# bldc_driver_board_easyeda.net
KiCad netlist of a schematic drawn in EasyEDA Pro
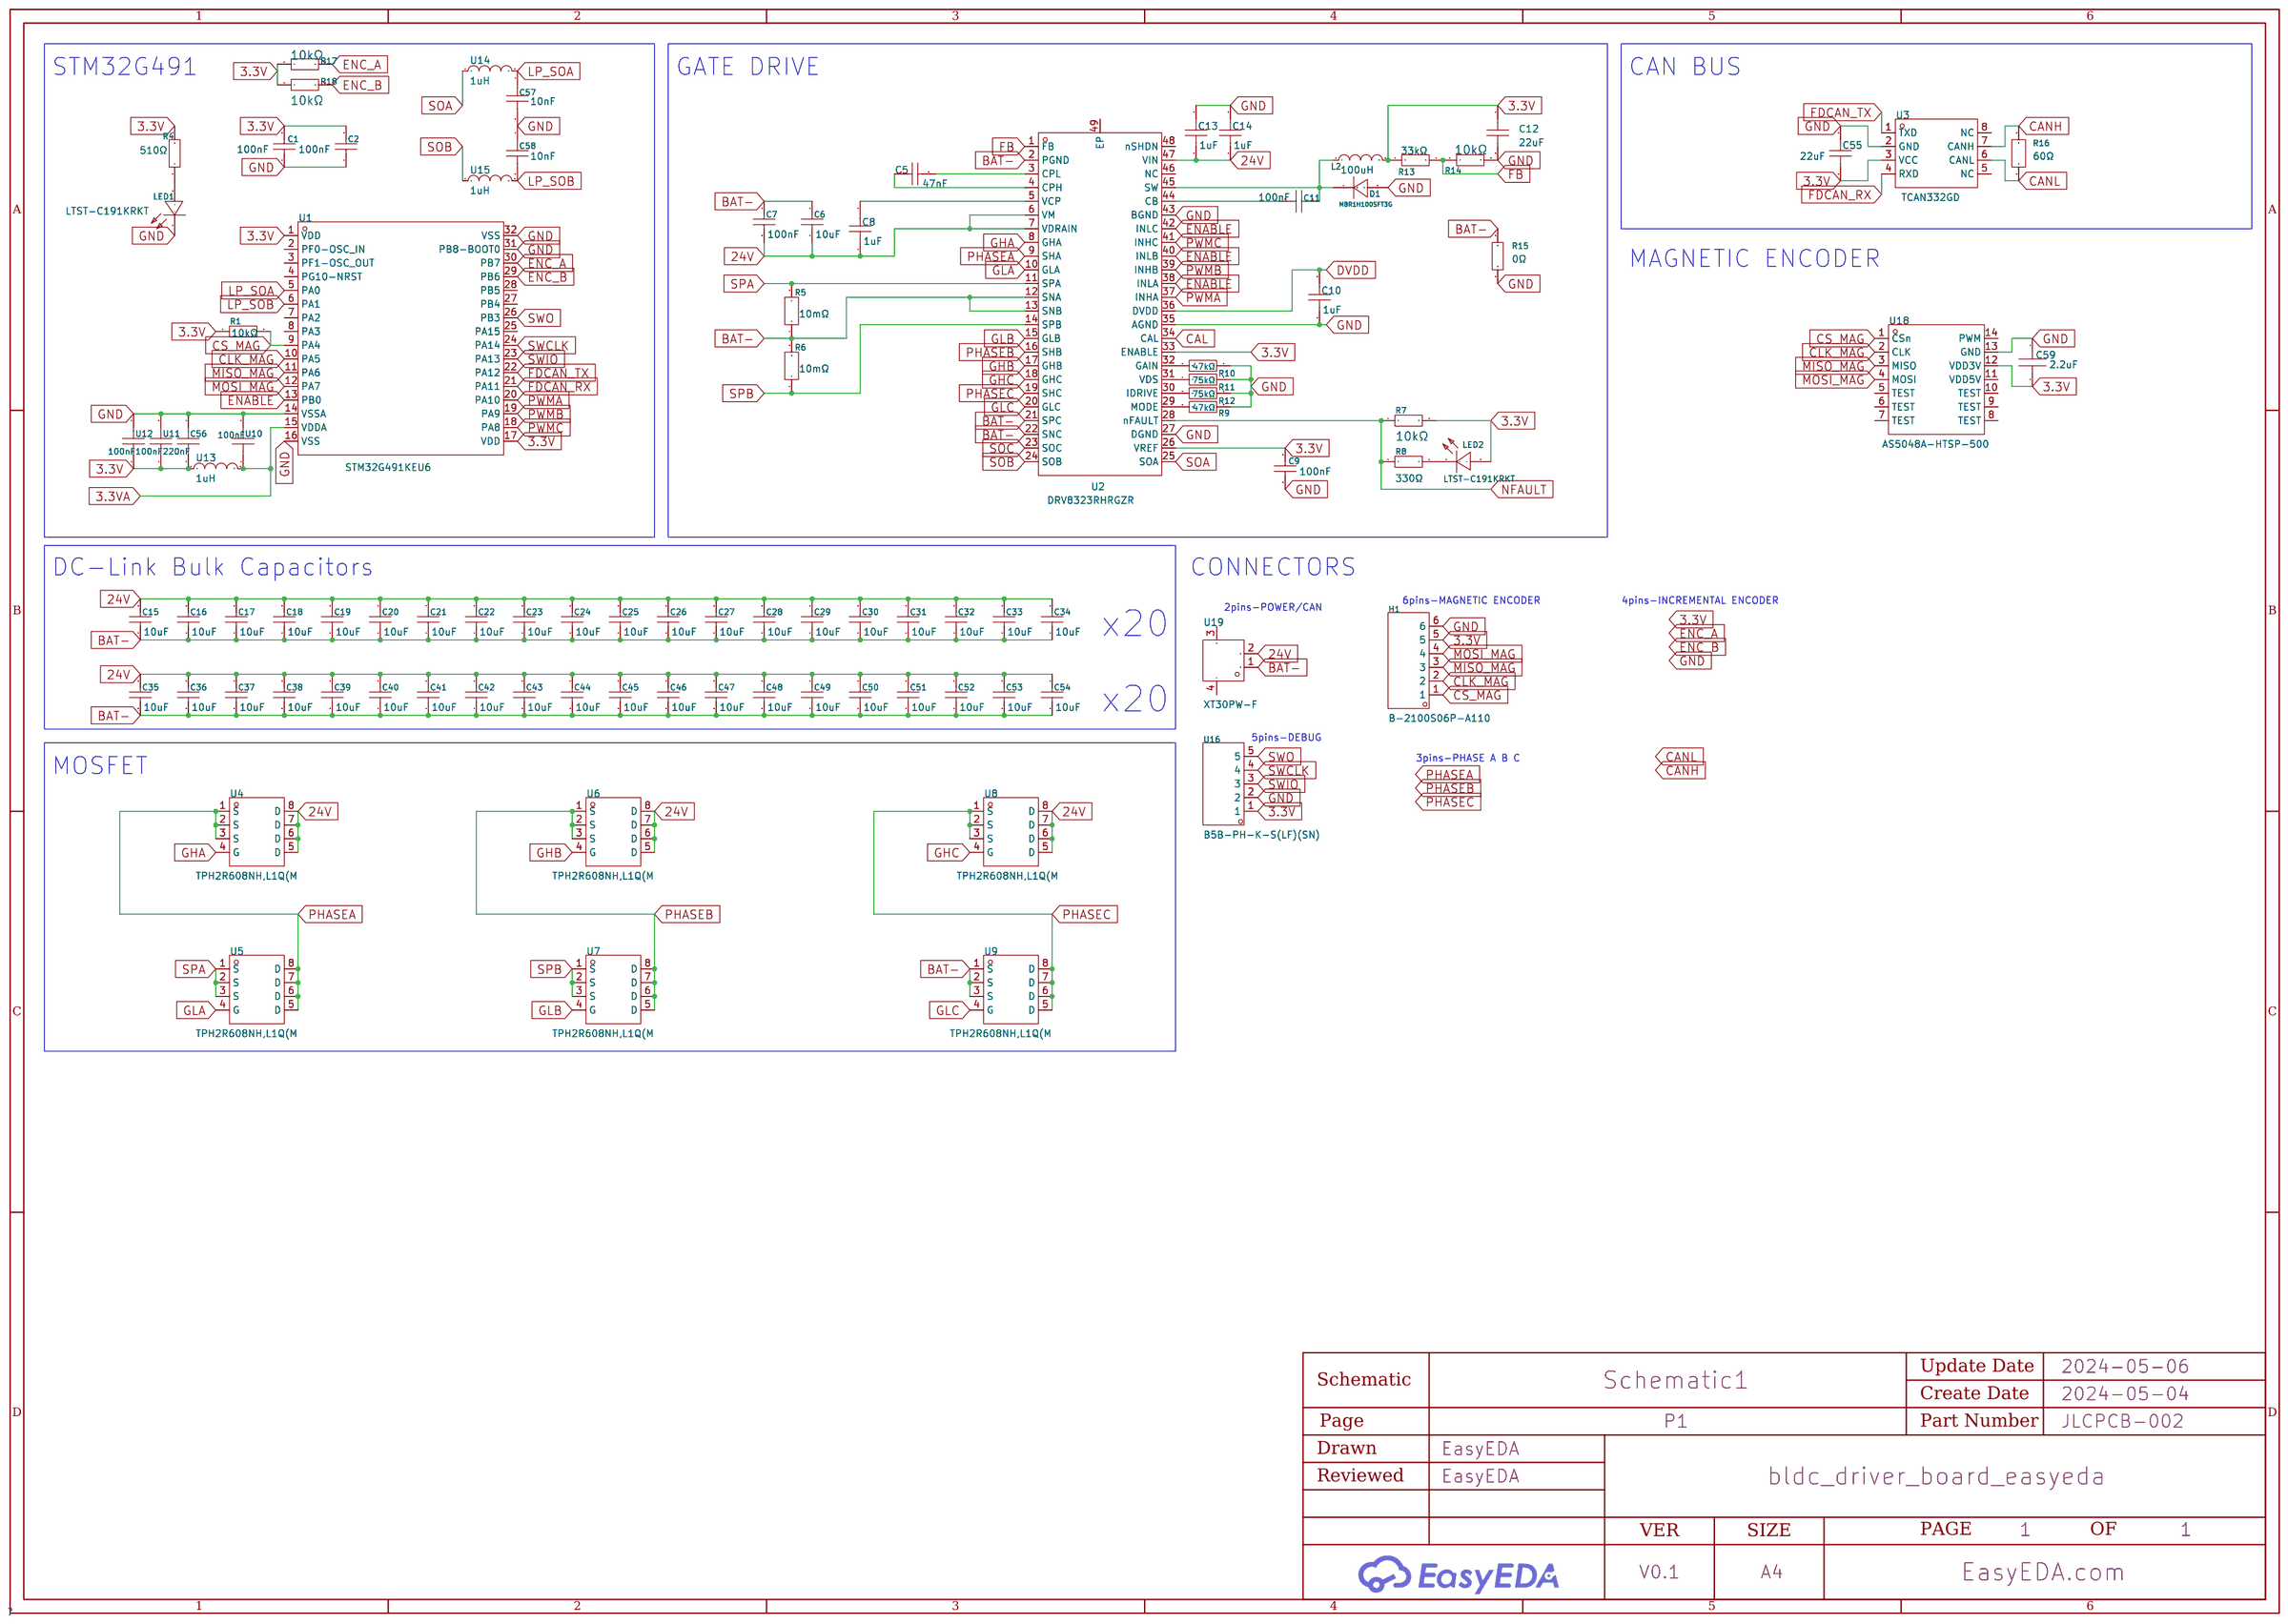
[diagram p0: schematic sheet]

(export (version "E")
  (design (tool "Eeschema 10.0.6"))
  (components
    (comp (ref "C1")
      (value "100nF")
      (footprint "easyedapro:C0603")
      (fields
        (field (name "Manufacturer Part") "CL10B104KO8NNNC")
        (field (name "Manufacturer") "SAMSUNG(三星)")
      )
      (libsource (lib "easyedapro") (part "CL10B104KO8NNNC"))
    )
    (comp (ref "C2")
      (value "100nF")
      (footprint "easyedapro:C0603")
      (fields
        (field (name "Manufacturer Part") "CL10B104KO8NNNC")
        (field (name "Manufacturer") "SAMSUNG(三星)")
      )
      (libsource (lib "easyedapro") (part "CL10B104KO8NNNC"))
    )
    (comp (ref "C5")
      (value "47nF")
      (footprint "easyedapro:C0805")
      (fields (field (name "Manufacturer Part") "0805B473K500NT") (field (name "Manufacturer") "FH(风华)"))
      (libsource (lib "easyedapro") (part "0805B473K500NT"))
    )
    (comp (ref "C6")
      (value "10uF")
      (footprint "easyedapro:C1206")
      (fields
        (field (name "Manufacturer Part") "CL31A106KBHNNNE")
        (field (name "Manufacturer") "SAMSUNG(三星)")
      )
      (libsource (lib "easyedapro") (part "CL31A106KBHNNNE"))
    )
    (comp (ref "C7")
      (value "100nF")
      (footprint "easyedapro:C1206")
      (fields (field (name "Manufacturer Part") "1206B104K500NT") (field (name "Manufacturer") "FH(风华)"))
      (libsource (lib "easyedapro") (part "1206B104K500NT"))
    )
    (comp (ref "C8")
      (value "1uF")
      (footprint "easyedapro:C0603")
      (fields
        (field (name "Manufacturer Part") "CL10A105KB8NNNC")
        (field (name "Manufacturer") "SAMSUNG(三星)")
      )
      (libsource (lib "easyedapro") (part "CL10A105KB8NNNC"))
    )
    (comp (ref "C9")
      (value "100nF")
      (footprint "easyedapro:C0603")
      (fields
        (field (name "Manufacturer Part") "CL10B104KO8NNNC")
        (field (name "Manufacturer") "SAMSUNG(三星)")
      )
      (libsource (lib "easyedapro") (part "CL10B104KO8NNNC"))
    )
    (comp (ref "C10")
      (value "1uF")
      (footprint "easyedapro:C0603")
      (fields
        (field (name "Manufacturer Part") "CL10A105KB8NNNC")
        (field (name "Manufacturer") "SAMSUNG(三星)")
      )
      (libsource (lib "easyedapro") (part "CL10A105KB8NNNC"))
    )
    (comp (ref "C11")
      (value "100nF")
      (footprint "easyedapro:C1206")
      (fields (field (name "Manufacturer Part") "1206B104K500NT") (field (name "Manufacturer") "FH(风华)"))
      (libsource (lib "easyedapro") (part "1206B104K500NT"))
    )
    (comp (ref "C12")
      (value "22uF")
      (footprint "easyedapro:C0603")
      (fields
        (field (name "Manufacturer Part") "CL10A226MQ8NRNE")
        (field (name "Manufacturer") "SAMSUNG(三星)")
      )
      (libsource (lib "easyedapro") (part "CL10A226MQ8NRNE"))
    )
    (comp (ref "C13")
      (value "1uF")
      (footprint "easyedapro:C0603")
      (fields
        (field (name "Manufacturer Part") "CL10A105KB8NNNC")
        (field (name "Manufacturer") "SAMSUNG(三星)")
      )
      (libsource (lib "easyedapro") (part "CL10A105KB8NNNC"))
    )
    (comp (ref "C14")
      (value "1uF")
      (footprint "easyedapro:C0603")
      (fields
        (field (name "Manufacturer Part") "CL10A105KB8NNNC")
        (field (name "Manufacturer") "SAMSUNG(三星)")
      )
      (libsource (lib "easyedapro") (part "CL10A105KB8NNNC"))
    )
    (comp (ref "C15")
      (value "10uF")
      (footprint "easyedapro:C1206")
      (fields
        (field (name "Manufacturer Part") "CL31A106KBHNNNE")
        (field (name "Manufacturer") "SAMSUNG(三星)")
      )
      (libsource (lib "easyedapro") (part "CL31A106KBHNNNE"))
    )
    (comp (ref "C16")
      (value "10uF")
      (footprint "easyedapro:C1206")
      (fields
        (field (name "Manufacturer Part") "CL31A106KBHNNNE")
        (field (name "Manufacturer") "SAMSUNG(三星)")
      )
      (libsource (lib "easyedapro") (part "CL31A106KBHNNNE"))
    )
    (comp (ref "C17")
      (value "10uF")
      (footprint "easyedapro:C1206")
      (fields
        (field (name "Manufacturer Part") "CL31A106KBHNNNE")
        (field (name "Manufacturer") "SAMSUNG(三星)")
      )
      (libsource (lib "easyedapro") (part "CL31A106KBHNNNE"))
    )
    (comp (ref "C18")
      (value "10uF")
      (footprint "easyedapro:C1206")
      (fields
        (field (name "Manufacturer Part") "CL31A106KBHNNNE")
        (field (name "Manufacturer") "SAMSUNG(三星)")
      )
      (libsource (lib "easyedapro") (part "CL31A106KBHNNNE"))
    )
    (comp (ref "C19")
      (value "10uF")
      (footprint "easyedapro:C1206")
      (fields
        (field (name "Manufacturer Part") "CL31A106KBHNNNE")
        (field (name "Manufacturer") "SAMSUNG(三星)")
      )
      (libsource (lib "easyedapro") (part "CL31A106KBHNNNE"))
    )
    (comp (ref "C20")
      (value "10uF")
      (footprint "easyedapro:C1206")
      (fields
        (field (name "Manufacturer Part") "CL31A106KBHNNNE")
        (field (name "Manufacturer") "SAMSUNG(三星)")
      )
      (libsource (lib "easyedapro") (part "CL31A106KBHNNNE"))
    )
    (comp (ref "C21")
      (value "10uF")
      (footprint "easyedapro:C1206")
      (fields
        (field (name "Manufacturer Part") "CL31A106KBHNNNE")
        (field (name "Manufacturer") "SAMSUNG(三星)")
      )
      (libsource (lib "easyedapro") (part "CL31A106KBHNNNE"))
    )
    (comp (ref "C22")
      (value "10uF")
      (footprint "easyedapro:C1206")
      (fields
        (field (name "Manufacturer Part") "CL31A106KBHNNNE")
        (field (name "Manufacturer") "SAMSUNG(三星)")
      )
      (libsource (lib "easyedapro") (part "CL31A106KBHNNNE"))
    )
    (comp (ref "C23")
      (value "10uF")
      (footprint "easyedapro:C1206")
      (fields
        (field (name "Manufacturer Part") "CL31A106KBHNNNE")
        (field (name "Manufacturer") "SAMSUNG(三星)")
      )
      (libsource (lib "easyedapro") (part "CL31A106KBHNNNE"))
    )
    (comp (ref "C24")
      (value "10uF")
      (footprint "easyedapro:C1206")
      (fields
        (field (name "Manufacturer Part") "CL31A106KBHNNNE")
        (field (name "Manufacturer") "SAMSUNG(三星)")
      )
      (libsource (lib "easyedapro") (part "CL31A106KBHNNNE"))
    )
    (comp (ref "C25")
      (value "10uF")
      (footprint "easyedapro:C1206")
      (fields
        (field (name "Manufacturer Part") "CL31A106KBHNNNE")
        (field (name "Manufacturer") "SAMSUNG(三星)")
      )
      (libsource (lib "easyedapro") (part "CL31A106KBHNNNE"))
    )
    (comp (ref "C26")
      (value "10uF")
      (footprint "easyedapro:C1206")
      (fields
        (field (name "Manufacturer Part") "CL31A106KBHNNNE")
        (field (name "Manufacturer") "SAMSUNG(三星)")
      )
      (libsource (lib "easyedapro") (part "CL31A106KBHNNNE"))
    )
    (comp (ref "C27")
      (value "10uF")
      (footprint "easyedapro:C1206")
      (fields
        (field (name "Manufacturer Part") "CL31A106KBHNNNE")
        (field (name "Manufacturer") "SAMSUNG(三星)")
      )
      (libsource (lib "easyedapro") (part "CL31A106KBHNNNE"))
    )
    (comp (ref "C28")
      (value "10uF")
      (footprint "easyedapro:C1206")
      (fields
        (field (name "Manufacturer Part") "CL31A106KBHNNNE")
        (field (name "Manufacturer") "SAMSUNG(三星)")
      )
      (libsource (lib "easyedapro") (part "CL31A106KBHNNNE"))
    )
    (comp (ref "C29")
      (value "10uF")
      (footprint "easyedapro:C1206")
      (fields
        (field (name "Manufacturer Part") "CL31A106KBHNNNE")
        (field (name "Manufacturer") "SAMSUNG(三星)")
      )
      (libsource (lib "easyedapro") (part "CL31A106KBHNNNE"))
    )
    (comp (ref "C30")
      (value "10uF")
      (footprint "easyedapro:C1206")
      (fields
        (field (name "Manufacturer Part") "CL31A106KBHNNNE")
        (field (name "Manufacturer") "SAMSUNG(三星)")
      )
      (libsource (lib "easyedapro") (part "CL31A106KBHNNNE"))
    )
    (comp (ref "C31")
      (value "10uF")
      (footprint "easyedapro:C1206")
      (fields
        (field (name "Manufacturer Part") "CL31A106KBHNNNE")
        (field (name "Manufacturer") "SAMSUNG(三星)")
      )
      (libsource (lib "easyedapro") (part "CL31A106KBHNNNE"))
    )
    (comp (ref "C32")
      (value "10uF")
      (footprint "easyedapro:C1206")
      (fields
        (field (name "Manufacturer Part") "CL31A106KBHNNNE")
        (field (name "Manufacturer") "SAMSUNG(三星)")
      )
      (libsource (lib "easyedapro") (part "CL31A106KBHNNNE"))
    )
    (comp (ref "C33")
      (value "10uF")
      (footprint "easyedapro:C1206")
      (fields
        (field (name "Manufacturer Part") "CL31A106KBHNNNE")
        (field (name "Manufacturer") "SAMSUNG(三星)")
      )
      (libsource (lib "easyedapro") (part "CL31A106KBHNNNE"))
    )
    (comp (ref "C34")
      (value "10uF")
      (footprint "easyedapro:C1206")
      (fields
        (field (name "Manufacturer Part") "CL31A106KBHNNNE")
        (field (name "Manufacturer") "SAMSUNG(三星)")
      )
      (libsource (lib "easyedapro") (part "CL31A106KBHNNNE"))
    )
    (comp (ref "C35")
      (value "10uF")
      (footprint "easyedapro:C1206")
      (fields
        (field (name "Manufacturer Part") "CL31A106KBHNNNE")
        (field (name "Manufacturer") "SAMSUNG(三星)")
      )
      (libsource (lib "easyedapro") (part "CL31A106KBHNNNE"))
    )
    (comp (ref "C36")
      (value "10uF")
      (footprint "easyedapro:C1206")
      (fields
        (field (name "Manufacturer Part") "CL31A106KBHNNNE")
        (field (name "Manufacturer") "SAMSUNG(三星)")
      )
      (libsource (lib "easyedapro") (part "CL31A106KBHNNNE"))
    )
    (comp (ref "C37")
      (value "10uF")
      (footprint "easyedapro:C1206")
      (fields
        (field (name "Manufacturer Part") "CL31A106KBHNNNE")
        (field (name "Manufacturer") "SAMSUNG(三星)")
      )
      (libsource (lib "easyedapro") (part "CL31A106KBHNNNE"))
    )
    (comp (ref "C38")
      (value "10uF")
      (footprint "easyedapro:C1206")
      (fields
        (field (name "Manufacturer Part") "CL31A106KBHNNNE")
        (field (name "Manufacturer") "SAMSUNG(三星)")
      )
      (libsource (lib "easyedapro") (part "CL31A106KBHNNNE"))
    )
    (comp (ref "C39")
      (value "10uF")
      (footprint "easyedapro:C1206")
      (fields
        (field (name "Manufacturer Part") "CL31A106KBHNNNE")
        (field (name "Manufacturer") "SAMSUNG(三星)")
      )
      (libsource (lib "easyedapro") (part "CL31A106KBHNNNE"))
    )
    (comp (ref "C40")
      (value "10uF")
      (footprint "easyedapro:C1206")
      (fields
        (field (name "Manufacturer Part") "CL31A106KBHNNNE")
        (field (name "Manufacturer") "SAMSUNG(三星)")
      )
      (libsource (lib "easyedapro") (part "CL31A106KBHNNNE"))
    )
    (comp (ref "C41")
      (value "10uF")
      (footprint "easyedapro:C1206")
      (fields
        (field (name "Manufacturer Part") "CL31A106KBHNNNE")
        (field (name "Manufacturer") "SAMSUNG(三星)")
      )
      (libsource (lib "easyedapro") (part "CL31A106KBHNNNE"))
    )
    (comp (ref "C42")
      (value "10uF")
      (footprint "easyedapro:C1206")
      (fields
        (field (name "Manufacturer Part") "CL31A106KBHNNNE")
        (field (name "Manufacturer") "SAMSUNG(三星)")
      )
      (libsource (lib "easyedapro") (part "CL31A106KBHNNNE"))
    )
    (comp (ref "C43")
      (value "10uF")
      (footprint "easyedapro:C1206")
      (fields
        (field (name "Manufacturer Part") "CL31A106KBHNNNE")
        (field (name "Manufacturer") "SAMSUNG(三星)")
      )
      (libsource (lib "easyedapro") (part "CL31A106KBHNNNE"))
    )
    (comp (ref "C44")
      (value "10uF")
      (footprint "easyedapro:C1206")
      (fields
        (field (name "Manufacturer Part") "CL31A106KBHNNNE")
        (field (name "Manufacturer") "SAMSUNG(三星)")
      )
      (libsource (lib "easyedapro") (part "CL31A106KBHNNNE"))
    )
    (comp (ref "C45")
      (value "10uF")
      (footprint "easyedapro:C1206")
      (fields
        (field (name "Manufacturer Part") "CL31A106KBHNNNE")
        (field (name "Manufacturer") "SAMSUNG(三星)")
      )
      (libsource (lib "easyedapro") (part "CL31A106KBHNNNE"))
    )
    (comp (ref "C46")
      (value "10uF")
      (footprint "easyedapro:C1206")
      (fields
        (field (name "Manufacturer Part") "CL31A106KBHNNNE")
        (field (name "Manufacturer") "SAMSUNG(三星)")
      )
      (libsource (lib "easyedapro") (part "CL31A106KBHNNNE"))
    )
    (comp (ref "C47")
      (value "10uF")
      (footprint "easyedapro:C1206")
      (fields
        (field (name "Manufacturer Part") "CL31A106KBHNNNE")
        (field (name "Manufacturer") "SAMSUNG(三星)")
      )
      (libsource (lib "easyedapro") (part "CL31A106KBHNNNE"))
    )
    (comp (ref "C48")
      (value "10uF")
      (footprint "easyedapro:C1206")
      (fields
        (field (name "Manufacturer Part") "CL31A106KBHNNNE")
        (field (name "Manufacturer") "SAMSUNG(三星)")
      )
      (libsource (lib "easyedapro") (part "CL31A106KBHNNNE"))
    )
    (comp (ref "C49")
      (value "10uF")
      (footprint "easyedapro:C1206")
      (fields
        (field (name "Manufacturer Part") "CL31A106KBHNNNE")
        (field (name "Manufacturer") "SAMSUNG(三星)")
      )
      (libsource (lib "easyedapro") (part "CL31A106KBHNNNE"))
    )
    (comp (ref "C50")
      (value "10uF")
      (footprint "easyedapro:C1206")
      (fields
        (field (name "Manufacturer Part") "CL31A106KBHNNNE")
        (field (name "Manufacturer") "SAMSUNG(三星)")
      )
      (libsource (lib "easyedapro") (part "CL31A106KBHNNNE"))
    )
    (comp (ref "C51")
      (value "10uF")
      (footprint "easyedapro:C1206")
      (fields
        (field (name "Manufacturer Part") "CL31A106KBHNNNE")
        (field (name "Manufacturer") "SAMSUNG(三星)")
      )
      (libsource (lib "easyedapro") (part "CL31A106KBHNNNE"))
    )
    (comp (ref "C52")
      (value "10uF")
      (footprint "easyedapro:C1206")
      (fields
        (field (name "Manufacturer Part") "CL31A106KBHNNNE")
        (field (name "Manufacturer") "SAMSUNG(三星)")
      )
      (libsource (lib "easyedapro") (part "CL31A106KBHNNNE"))
    )
    (comp (ref "C53")
      (value "10uF")
      (footprint "easyedapro:C1206")
      (fields
        (field (name "Manufacturer Part") "CL31A106KBHNNNE")
        (field (name "Manufacturer") "SAMSUNG(三星)")
      )
      (libsource (lib "easyedapro") (part "CL31A106KBHNNNE"))
    )
    (comp (ref "C54")
      (value "10uF")
      (footprint "easyedapro:C1206")
      (fields
        (field (name "Manufacturer Part") "CL31A106KBHNNNE")
        (field (name "Manufacturer") "SAMSUNG(三星)")
      )
      (libsource (lib "easyedapro") (part "CL31A106KBHNNNE"))
    )
    (comp (ref "C55")
      (value "22uF")
      (footprint "easyedapro:C0603")
      (fields
        (field (name "Manufacturer Part") "CL10A226MQ8NRNE")
        (field (name "Manufacturer") "SAMSUNG(三星)")
      )
      (libsource (lib "easyedapro") (part "CL10A226MQ8NRNE"))
    )
    (comp (ref "C56")
      (value "220nF")
      (footprint "easyedapro:C0201")
      (fields (field (name "Manufacturer Part") "C0603X5R0J224KT00NN") (field (name "Manufacturer") "TDK"))
      (libsource (lib "easyedapro") (part "C0603X5R0J224KT00NN"))
    )
    (comp (ref "C57")
      (value "10nF")
      (footprint "easyedapro:C01005")
      (fields
        (field (name "Manufacturer Part") "CC0100KRX5R5BB103")
        (field (name "Manufacturer") "YAGEO(国巨)")
      )
      (libsource (lib "easyedapro") (part "CC0100KRX5R5BB103"))
    )
    (comp (ref "C58")
      (value "10nF")
      (footprint "easyedapro:C01005")
      (fields
        (field (name "Manufacturer Part") "CC0100KRX5R5BB103")
        (field (name "Manufacturer") "YAGEO(国巨)")
      )
      (libsource (lib "easyedapro") (part "CC0100KRX5R5BB103"))
    )
    (comp (ref "C59")
      (value "2.2uF")
      (footprint "easyedapro:C0402")
      (fields
        (field (name "Manufacturer Part") "CL05A225MQ5NSNC")
        (field (name "Manufacturer") "SAMSUNG(三星)")
      )
      (libsource (lib "easyedapro") (part "CL05A225MQ5NSNC"))
    )
    (comp (ref "D1")
      (value "MBR1H100SFT3G")
      (footprint "easyedapro:SOD-123F_L2.8-W1.8-LS3.7-RD")
      (fields (field (name "Manufacturer") "onsemi(安森美)"))
      (libsource (lib "easyedapro") (part "MBR1H100SFT3G"))
    )
    (comp (ref "H1")
      (value "B-2100S06P-A110")
      (footprint "easyedapro:HDR-TH_6P-P2.54-V_Z-211-0611-0021-001")
      (fields (field (name "Manufacturer") "Ckmtw(灿科盟)"))
      (libsource (lib "easyedapro") (part "210S-1*6P L=11.6MMGold-plated black"))
    )
    (comp (ref "L2")
      (value "100uH")
      (footprint "easyedapro:IND-SMD_L4.0-W4.0")
      (fields
        (field (name "Manufacturer Part") "ASPIAIG-S4035-101M-T")
        (field (name "Manufacturer") "ABRACON")
      )
      (libsource (lib "easyedapro") (part "ASPIAIG-S4035-101M-T"))
    )
    (comp (ref "LED1")
      (value "LTST-C191KRKT")
      (footprint "easyedapro:LED0603-RD")
      (fields (field (name "Manufacturer") "LITEON(光宝)"))
      (libsource (lib "easyedapro") (part "LTST-C191KRKT"))
    )
    (comp (ref "LED2")
      (value "LTST-C191KRKT")
      (footprint "easyedapro:LED0603-RD")
      (fields (field (name "Manufacturer") "LITEON(光宝)"))
      (libsource (lib "easyedapro") (part "LTST-C191KRKT"))
    )
    (comp (ref "R1")
      (value "10kΩ")
      (footprint "easyedapro:R0603")
      (fields
        (field (name "Manufacturer Part") "0603WAF1002T5E")
        (field (name "Manufacturer") "UNI-ROYAL(厚声)")
      )
      (libsource (lib "easyedapro") (part "0603WAF1002T5E"))
    )
    (comp (ref "R4")
      (value "510Ω")
      (footprint "easyedapro:R0603")
      (fields
        (field (name "Manufacturer Part") "0603WAF5100T5E")
        (field (name "Manufacturer") "UNI-ROYAL(厚声)")
      )
      (libsource (lib "easyedapro") (part "0603WAF5100T5E"))
    )
    (comp (ref "R5")
      (value "10mΩ")
      (footprint "easyedapro:RES-SMD_L6.4-W3.2-R2512")
      (fields
        (field (name "Manufacturer Part") "HoJLR2512-3W-10mR-1%")
        (field (name "Manufacturer") "Milliohm(毫欧)")
      )
      (libsource (lib "easyedapro") (part "HOJLR2512-3W-10MR-1%"))
    )
    (comp (ref "R6")
      (value "10mΩ")
      (footprint "easyedapro:RES-SMD_L6.4-W3.2-R2512")
      (fields
        (field (name "Manufacturer Part") "HoJLR2512-3W-10mR-1%")
        (field (name "Manufacturer") "Milliohm(毫欧)")
      )
      (libsource (lib "easyedapro") (part "HOJLR2512-3W-10MR-1%"))
    )
    (comp (ref "R7")
      (value "10kΩ")
      (footprint "easyedapro:R0603")
      (fields
        (field (name "Manufacturer Part") "0603WAF1002T5E")
        (field (name "Manufacturer") "UNI-ROYAL(厚声)")
      )
      (libsource (lib "easyedapro") (part "0603WAF1002T5E"))
    )
    (comp (ref "R8")
      (value "330Ω")
      (footprint "easyedapro:R0603")
      (fields
        (field (name "Manufacturer Part") "0603WAF3300T5E")
        (field (name "Manufacturer") "UNI-ROYAL(厚声)")
      )
      (libsource (lib "easyedapro") (part "0603WAF3300T5E"))
    )
    (comp (ref "R9")
      (value "47kΩ")
      (footprint "easyedapro:R0603")
      (fields
        (field (name "Manufacturer Part") "0603WAF4702T5E")
        (field (name "Manufacturer") "UNI-ROYAL(厚声)")
      )
      (libsource (lib "easyedapro") (part "0603WAF4702T5E"))
    )
    (comp (ref "R10")
      (value "47kΩ")
      (footprint "easyedapro:R0603")
      (fields
        (field (name "Manufacturer Part") "0603WAF4702T5E")
        (field (name "Manufacturer") "UNI-ROYAL(厚声)")
      )
      (libsource (lib "easyedapro") (part "0603WAF4702T5E"))
    )
    (comp (ref "R11")
      (value "75kΩ")
      (footprint "easyedapro:R0603")
      (fields
        (field (name "Manufacturer Part") "0603WAF7502T5E")
        (field (name "Manufacturer") "UNI-ROYAL(厚声)")
      )
      (libsource (lib "easyedapro") (part "0603WAF7502T5E"))
    )
    (comp (ref "R12")
      (value "75kΩ")
      (footprint "easyedapro:R0603")
      (fields
        (field (name "Manufacturer Part") "0603WAF7502T5E")
        (field (name "Manufacturer") "UNI-ROYAL(厚声)")
      )
      (libsource (lib "easyedapro") (part "0603WAF7502T5E"))
    )
    (comp (ref "R13")
      (value "33kΩ")
      (footprint "easyedapro:R0603")
      (fields
        (field (name "Manufacturer Part") "0603WAF3302T5E")
        (field (name "Manufacturer") "UNI-ROYAL(厚声)")
      )
      (libsource (lib "easyedapro") (part "0603WAF3302T5E"))
    )
    (comp (ref "R14")
      (value "10kΩ")
      (footprint "easyedapro:R0603")
      (fields
        (field (name "Manufacturer Part") "0603WAF1002T5E")
        (field (name "Manufacturer") "UNI-ROYAL(厚声)")
      )
      (libsource (lib "easyedapro") (part "0603WAF1002T5E"))
    )
    (comp (ref "R15")
      (value "0Ω")
      (footprint "easyedapro:R1206")
      (fields
        (field (name "Manufacturer Part") "1206W4F0000T5E")
        (field (name "Manufacturer") "UNI-ROYAL(厚声)")
      )
      (libsource (lib "easyedapro") (part "1206W4F0000T5E"))
    )
    (comp (ref "R16")
      (value "60Ω")
      (footprint "easyedapro:R0603")
      (fields (field (name "Manufacturer Part") "RTT0360R0FTP") (field (name "Manufacturer") "RALEC(旺诠)"))
      (libsource (lib "easyedapro") (part "RTT0360R0FTP"))
    )
    (comp (ref "R17")
      (value "10kΩ")
      (footprint "easyedapro:R0603")
      (fields
        (field (name "Manufacturer Part") "0603WAF1002T5E")
        (field (name "Manufacturer") "UNI-ROYAL(厚声)")
      )
      (libsource (lib "easyedapro") (part "0603WAF1002T5E"))
    )
    (comp (ref "R18")
      (value "10kΩ")
      (footprint "easyedapro:R0603")
      (fields
        (field (name "Manufacturer Part") "0603WAF1002T5E")
        (field (name "Manufacturer") "UNI-ROYAL(厚声)")
      )
      (libsource (lib "easyedapro") (part "0603WAF1002T5E"))
    )
    (comp (ref "U1")
      (value "STM32G491KEU6")
      (footprint "easyedapro:UFQFPN-32_L5.0-W5.0-P0.50-TL-1")
      (fields (field (name "Manufacturer") "ST(意法半导体)"))
      (libsource (lib "easyedapro") (part "STM32G491KEU6"))
    )
    (comp (ref "U2")
      (value "DRV8323RHRGZR")
      (footprint "easyedapro:VQFN-48_L7.0-W7.0-P0.50-TL-EP5.1")
      (fields (field (name "Manufacturer") "TI(德州仪器)"))
      (libsource (lib "easyedapro") (part "DRV8323RHRGZR"))
    )
    (comp (ref "U3")
      (value "TCAN332GD")
      (footprint "easyedapro:SOIC-8_L4.9-W3.9-P1.27-LS6.0-BL")
      (fields (field (name "Manufacturer") "TI(德州仪器)"))
      (libsource (lib "easyedapro") (part "TCAN332GD"))
    )
    (comp (ref "U4")
      (value "TPH2R608NH,L1Q(M")
      (footprint "easyedapro:POWERVDFN-8_L5.0-W5.0-P1.27-LS6.0-BL")
      (fields (field (name "Manufacturer") "TOSHIBA(东芝)"))
      (libsource (lib "easyedapro") (part "TPH2R608NH,L1Q(M"))
    )
    (comp (ref "U5")
      (value "TPH2R608NH,L1Q(M")
      (footprint "easyedapro:POWERVDFN-8_L5.0-W5.0-P1.27-LS6.0-BL")
      (fields (field (name "Manufacturer") "TOSHIBA(东芝)"))
      (libsource (lib "easyedapro") (part "TPH2R608NH,L1Q(M"))
    )
    (comp (ref "U6")
      (value "TPH2R608NH,L1Q(M")
      (footprint "easyedapro:POWERVDFN-8_L5.0-W5.0-P1.27-LS6.0-BL")
      (fields (field (name "Manufacturer") "TOSHIBA(东芝)"))
      (libsource (lib "easyedapro") (part "TPH2R608NH,L1Q(M"))
    )
    (comp (ref "U7")
      (value "TPH2R608NH,L1Q(M")
      (footprint "easyedapro:POWERVDFN-8_L5.0-W5.0-P1.27-LS6.0-BL")
      (fields (field (name "Manufacturer") "TOSHIBA(东芝)"))
      (libsource (lib "easyedapro") (part "TPH2R608NH,L1Q(M"))
    )
    (comp (ref "U8")
      (value "TPH2R608NH,L1Q(M")
      (footprint "easyedapro:POWERVDFN-8_L5.0-W5.0-P1.27-LS6.0-BL")
      (fields (field (name "Manufacturer") "TOSHIBA(东芝)"))
      (libsource (lib "easyedapro") (part "TPH2R608NH,L1Q(M"))
    )
    (comp (ref "U9")
      (value "TPH2R608NH,L1Q(M")
      (footprint "easyedapro:POWERVDFN-8_L5.0-W5.0-P1.27-LS6.0-BL")
      (fields (field (name "Manufacturer") "TOSHIBA(东芝)"))
      (libsource (lib "easyedapro") (part "TPH2R608NH,L1Q(M"))
    )
    (comp (ref "U10")
      (value "100nF")
      (footprint "easyedapro:C0603")
      (fields (field (name "Manufacturer Part") "06036D104KAT2A") (field (name "Manufacturer") "Kyocera AVX"))
      (libsource (lib "easyedapro") (part "06036D104KAT2A"))
    )
    (comp (ref "U11")
      (value "100nF")
      (footprint "easyedapro:C0603")
      (fields (field (name "Manufacturer Part") "06036D104KAT2A") (field (name "Manufacturer") "Kyocera AVX"))
      (libsource (lib "easyedapro") (part "06036D104KAT2A"))
    )
    (comp (ref "U12")
      (value "100nF")
      (footprint "easyedapro:C0603")
      (fields (field (name "Manufacturer Part") "06036D104KAT2A") (field (name "Manufacturer") "Kyocera AVX"))
      (libsource (lib "easyedapro") (part "06036D104KAT2A"))
    )
    (comp (ref "U13")
      (value "1uH")
      (footprint "easyedapro:L0603")
      (fields (field (name "Manufacturer Part") "YL160808-1R0K") (field (name "Manufacturer") "YJYCOIN(益嘉源)"))
      (libsource (lib "easyedapro") (part "YL160808-1R0K"))
    )
    (comp (ref "U14")
      (value "1uH")
      (footprint "easyedapro:L0603")
      (fields (field (name "Manufacturer Part") "YL160808-1R0K") (field (name "Manufacturer") "YJYCOIN(益嘉源)"))
      (libsource (lib "easyedapro") (part "YL160808-1R0K"))
    )
    (comp (ref "U15")
      (value "1uH")
      (footprint "easyedapro:L0603")
      (fields (field (name "Manufacturer Part") "YL160808-1R0K") (field (name "Manufacturer") "YJYCOIN(益嘉源)"))
      (libsource (lib "easyedapro") (part "YL160808-1R0K"))
    )
    (comp (ref "U16")
      (value "B5B-PH-K-S(LF)(SN)")
      (footprint "easyedapro:CONN-TH_B5B-PH-K-S-LF-SN")
      (fields (field (name "Manufacturer") "JST"))
      (libsource (lib "easyedapro") (part "B5B-PH-K-S-(LF)(SN)"))
    )
    (comp (ref "U18")
      (value "AS5048A-HTSP-500")
      (footprint "easyedapro:TSSOP-14_L5.0-W4.4-P0.65-LS6.4-BL")
      (fields (field (name "Manufacturer") "ams(艾迈斯半导体)"))
      (libsource (lib "easyedapro") (part "AS5048A-HTSP-500"))
    )
    (comp (ref "U19")
      (value "XT30PW-F")
      (footprint "easyedapro:CONN-TH_XT30PW-F-1")
      (fields (field (name "Manufacturer") "AMASS(艾迈斯)"))
      (libsource (lib "easyedapro") (part "XT30PW-F"))
    )
  )
  (nets
    (net (code "1") (name "3.3V") (class "Default")
      (node (ref "C1") (pin "2") (pinfunction "2_2") (pintype "input"))
      (node (ref "C12") (pin "1") (pinfunction "1_1") (pintype "unspecified"))
      (node (ref "C2") (pin "2") (pinfunction "2_2") (pintype "input"))
      (node (ref "C55") (pin "2") (pinfunction "2_2") (pintype "unspecified"))
      (node (ref "C56") (pin "2") (pinfunction "2_2") (pintype "input"))
      (node (ref "C59") (pin "2") (pinfunction "2_2") (pintype "unspecified"))
      (node (ref "C9") (pin "2") (pinfunction "2_2") (pintype "input"))
      (node (ref "H1") (pin "5") (pinfunction "5_5") (pintype "input"))
      (node (ref "L2") (pin "2") (pinfunction "2_2") (pintype "input"))
      (node (ref "LED2") (pin "2") (pinfunction "+_2") (pintype "input"))
      (node (ref "R1") (pin "1") (pinfunction "1_1") (pintype "input"))
      (node (ref "R13") (pin "1") (pinfunction "1_1") (pintype "input"))
      (node (ref "R17") (pin "1") (pinfunction "1_1") (pintype "input"))
      (node (ref "R18") (pin "1") (pinfunction "1_1") (pintype "input"))
      (node (ref "R4") (pin "2") (pinfunction "2_2") (pintype "input"))
      (node (ref "R7") (pin "2") (pinfunction "2_2") (pintype "input"))
      (node (ref "U1") (pin "1") (pinfunction "VDD_1") (pintype "unspecified"))
      (node (ref "U1") (pin "17") (pinfunction "VDD_17") (pintype "unspecified"))
      (node (ref "U11") (pin "1") (pinfunction "1_1") (pintype "unspecified"))
      (node (ref "U12") (pin "1") (pinfunction "1_1") (pintype "unspecified"))
      (node (ref "U13") (pin "1") (pinfunction "1_1") (pintype "unspecified"))
      (node (ref "U16") (pin "1") (pinfunction "1_1") (pintype "input"))
      (node (ref "U18") (pin "12") (pinfunction "VDD3V_12") (pintype "unspecified"))
      (node (ref "U2") (pin "26") (pinfunction "VREF_26") (pintype "input"))
      (node (ref "U2") (pin "33") (pinfunction "ENABLE_33") (pintype "input"))
      (node (ref "U3") (pin "3") (pinfunction "VCC_3") (pintype "unspecified"))
    )
    (net (code "2") (name "3.3VA") (class "Default")
      (node (ref "U1") (pin "15") (pinfunction "VDDA_15") (pintype "unspecified"))
      (node (ref "U10") (pin "1") (pinfunction "1_1") (pintype "unspecified"))
      (node (ref "U13") (pin "2") (pinfunction "2_2") (pintype "unspecified"))
    )
    (net (code "3") (name "24V") (class "Default")
      (node (ref "C13") (pin "1") (pinfunction "1_1") (pintype "unspecified"))
      (node (ref "C14") (pin "1") (pinfunction "1_1") (pintype "unspecified"))
      (node (ref "C15") (pin "2") (pinfunction "2_2") (pintype "input"))
      (node (ref "C16") (pin "2") (pinfunction "2_2") (pintype "input"))
      (node (ref "C17") (pin "2") (pinfunction "2_2") (pintype "input"))
      (node (ref "C18") (pin "2") (pinfunction "2_2") (pintype "input"))
      (node (ref "C19") (pin "2") (pinfunction "2_2") (pintype "input"))
      (node (ref "C20") (pin "2") (pinfunction "2_2") (pintype "input"))
      (node (ref "C21") (pin "2") (pinfunction "2_2") (pintype "input"))
      (node (ref "C22") (pin "2") (pinfunction "2_2") (pintype "input"))
      (node (ref "C23") (pin "2") (pinfunction "2_2") (pintype "input"))
      (node (ref "C24") (pin "2") (pinfunction "2_2") (pintype "input"))
      (node (ref "C25") (pin "2") (pinfunction "2_2") (pintype "input"))
      (node (ref "C26") (pin "2") (pinfunction "2_2") (pintype "input"))
      (node (ref "C27") (pin "2") (pinfunction "2_2") (pintype "input"))
      (node (ref "C28") (pin "2") (pinfunction "2_2") (pintype "input"))
      (node (ref "C29") (pin "2") (pinfunction "2_2") (pintype "input"))
      (node (ref "C30") (pin "2") (pinfunction "2_2") (pintype "input"))
      (node (ref "C31") (pin "2") (pinfunction "2_2") (pintype "input"))
      (node (ref "C32") (pin "2") (pinfunction "2_2") (pintype "input"))
      (node (ref "C33") (pin "2") (pinfunction "2_2") (pintype "input"))
      (node (ref "C34") (pin "2") (pinfunction "2_2") (pintype "input"))
      (node (ref "C35") (pin "2") (pinfunction "2_2") (pintype "input"))
      (node (ref "C36") (pin "2") (pinfunction "2_2") (pintype "input"))
      (node (ref "C37") (pin "2") (pinfunction "2_2") (pintype "input"))
      (node (ref "C38") (pin "2") (pinfunction "2_2") (pintype "input"))
      (node (ref "C39") (pin "2") (pinfunction "2_2") (pintype "input"))
      (node (ref "C40") (pin "2") (pinfunction "2_2") (pintype "input"))
      (node (ref "C41") (pin "2") (pinfunction "2_2") (pintype "input"))
      (node (ref "C42") (pin "2") (pinfunction "2_2") (pintype "input"))
      (node (ref "C43") (pin "2") (pinfunction "2_2") (pintype "input"))
      (node (ref "C44") (pin "2") (pinfunction "2_2") (pintype "input"))
      (node (ref "C45") (pin "2") (pinfunction "2_2") (pintype "input"))
      (node (ref "C46") (pin "2") (pinfunction "2_2") (pintype "input"))
      (node (ref "C47") (pin "2") (pinfunction "2_2") (pintype "input"))
      (node (ref "C48") (pin "2") (pinfunction "2_2") (pintype "input"))
      (node (ref "C49") (pin "2") (pinfunction "2_2") (pintype "input"))
      (node (ref "C50") (pin "2") (pinfunction "2_2") (pintype "input"))
      (node (ref "C51") (pin "2") (pinfunction "2_2") (pintype "input"))
      (node (ref "C52") (pin "2") (pinfunction "2_2") (pintype "input"))
      (node (ref "C53") (pin "2") (pinfunction "2_2") (pintype "input"))
      (node (ref "C54") (pin "2") (pinfunction "2_2") (pintype "input"))
      (node (ref "C6") (pin "1") (pinfunction "1_1") (pintype "input"))
      (node (ref "C7") (pin "1") (pinfunction "1_1") (pintype "input"))
      (node (ref "C8") (pin "1") (pinfunction "1_1") (pintype "unspecified"))
      (node (ref "U19") (pin "2") (pinfunction "2_2") (pintype "unspecified"))
      (node (ref "U2") (pin "47") (pinfunction "VIN_47") (pintype "input"))
      (node (ref "U2") (pin "6") (pinfunction "VM_6") (pintype "input"))
      (node (ref "U2") (pin "7") (pinfunction "VDRAIN_7") (pintype "input"))
      (node (ref "U4") (pin "5") (pinfunction "D_5") (pintype "input"))
      (node (ref "U4") (pin "6") (pinfunction "D_6") (pintype "input"))
      (node (ref "U4") (pin "7") (pinfunction "D_7") (pintype "input"))
      (node (ref "U4") (pin "8") (pinfunction "D_8") (pintype "input"))
      (node (ref "U6") (pin "5") (pinfunction "D_5") (pintype "input"))
      (node (ref "U6") (pin "6") (pinfunction "D_6") (pintype "input"))
      (node (ref "U6") (pin "7") (pinfunction "D_7") (pintype "input"))
      (node (ref "U6") (pin "8") (pinfunction "D_8") (pintype "input"))
      (node (ref "U8") (pin "5") (pinfunction "D_5") (pintype "input"))
      (node (ref "U8") (pin "6") (pinfunction "D_6") (pintype "input"))
      (node (ref "U8") (pin "7") (pinfunction "D_7") (pintype "input"))
      (node (ref "U8") (pin "8") (pinfunction "D_8") (pintype "input"))
    )
    (net (code "4") (name "BAT-") (class "Default")
      (node (ref "C15") (pin "1") (pinfunction "1_1") (pintype "input"))
      (node (ref "C16") (pin "1") (pinfunction "1_1") (pintype "input"))
      (node (ref "C17") (pin "1") (pinfunction "1_1") (pintype "input"))
      (node (ref "C18") (pin "1") (pinfunction "1_1") (pintype "input"))
      (node (ref "C19") (pin "1") (pinfunction "1_1") (pintype "input"))
      (node (ref "C20") (pin "1") (pinfunction "1_1") (pintype "input"))
      (node (ref "C21") (pin "1") (pinfunction "1_1") (pintype "input"))
      (node (ref "C22") (pin "1") (pinfunction "1_1") (pintype "input"))
      (node (ref "C23") (pin "1") (pinfunction "1_1") (pintype "input"))
      (node (ref "C24") (pin "1") (pinfunction "1_1") (pintype "input"))
      (node (ref "C25") (pin "1") (pinfunction "1_1") (pintype "input"))
      (node (ref "C26") (pin "1") (pinfunction "1_1") (pintype "input"))
      (node (ref "C27") (pin "1") (pinfunction "1_1") (pintype "input"))
      (node (ref "C28") (pin "1") (pinfunction "1_1") (pintype "input"))
      (node (ref "C29") (pin "1") (pinfunction "1_1") (pintype "input"))
      (node (ref "C30") (pin "1") (pinfunction "1_1") (pintype "input"))
      (node (ref "C31") (pin "1") (pinfunction "1_1") (pintype "input"))
      (node (ref "C32") (pin "1") (pinfunction "1_1") (pintype "input"))
      (node (ref "C33") (pin "1") (pinfunction "1_1") (pintype "input"))
      (node (ref "C34") (pin "1") (pinfunction "1_1") (pintype "input"))
      (node (ref "C35") (pin "1") (pinfunction "1_1") (pintype "input"))
      (node (ref "C36") (pin "1") (pinfunction "1_1") (pintype "input"))
      (node (ref "C37") (pin "1") (pinfunction "1_1") (pintype "input"))
      (node (ref "C38") (pin "1") (pinfunction "1_1") (pintype "input"))
      (node (ref "C39") (pin "1") (pinfunction "1_1") (pintype "input"))
      (node (ref "C40") (pin "1") (pinfunction "1_1") (pintype "input"))
      (node (ref "C41") (pin "1") (pinfunction "1_1") (pintype "input"))
      (node (ref "C42") (pin "1") (pinfunction "1_1") (pintype "input"))
      (node (ref "C43") (pin "1") (pinfunction "1_1") (pintype "input"))
      (node (ref "C44") (pin "1") (pinfunction "1_1") (pintype "input"))
      (node (ref "C45") (pin "1") (pinfunction "1_1") (pintype "input"))
      (node (ref "C46") (pin "1") (pinfunction "1_1") (pintype "input"))
      (node (ref "C47") (pin "1") (pinfunction "1_1") (pintype "input"))
      (node (ref "C48") (pin "1") (pinfunction "1_1") (pintype "input"))
      (node (ref "C49") (pin "1") (pinfunction "1_1") (pintype "input"))
      (node (ref "C50") (pin "1") (pinfunction "1_1") (pintype "input"))
      (node (ref "C51") (pin "1") (pinfunction "1_1") (pintype "input"))
      (node (ref "C52") (pin "1") (pinfunction "1_1") (pintype "input"))
      (node (ref "C53") (pin "1") (pinfunction "1_1") (pintype "input"))
      (node (ref "C54") (pin "1") (pinfunction "1_1") (pintype "input"))
      (node (ref "C6") (pin "2") (pinfunction "2_2") (pintype "input"))
      (node (ref "C7") (pin "2") (pinfunction "2_2") (pintype "input"))
      (node (ref "R15") (pin "2") (pinfunction "2_2") (pintype "input"))
      (node (ref "R5") (pin "1") (pinfunction "1_1") (pintype "input"))
      (node (ref "R6") (pin "2") (pinfunction "2_2") (pintype "input"))
      (node (ref "U19") (pin "1") (pinfunction "1_1") (pintype "unspecified"))
      (node (ref "U2") (pin "12") (pinfunction "SNA_12") (pintype "input"))
      (node (ref "U2") (pin "13") (pinfunction "SNB_13") (pintype "input"))
      (node (ref "U2") (pin "2") (pinfunction "PGND_2") (pintype "input"))
      (node (ref "U2") (pin "21") (pinfunction "SPC_21") (pintype "input"))
      (node (ref "U2") (pin "22") (pinfunction "SNC_22") (pintype "input"))
      (node (ref "U9") (pin "1") (pinfunction "S_1") (pintype "input"))
      (node (ref "U9") (pin "2") (pinfunction "S_2") (pintype "input"))
      (node (ref "U9") (pin "3") (pinfunction "S_3") (pintype "input"))
    )
    (net (code "5") (name "CAL") (class "Default")
      (node (ref "U2") (pin "34") (pinfunction "CAL_34") (pintype "input"))
    )
    (net (code "6") (name "CANH") (class "Default")
      (node (ref "R16") (pin "2") (pinfunction "2_2") (pintype "input"))
      (node (ref "U3") (pin "7") (pinfunction "CANH_7") (pintype "unspecified"))
    )
    (net (code "7") (name "CANL") (class "Default")
      (node (ref "R16") (pin "1") (pinfunction "1_1") (pintype "input"))
      (node (ref "U3") (pin "6") (pinfunction "CANL_6") (pintype "unspecified"))
    )
    (net (code "8") (name "CLK_MAG") (class "Default")
      (node (ref "H1") (pin "2") (pinfunction "2_2") (pintype "input"))
      (node (ref "U1") (pin "10") (pinfunction "PA5_10") (pintype "unspecified"))
      (node (ref "U18") (pin "2") (pinfunction "CLK_2") (pintype "unspecified"))
    )
    (net (code "9") (name "CS_MAG") (class "Default")
      (node (ref "H1") (pin "1") (pinfunction "1_1") (pintype "input"))
      (node (ref "R1") (pin "2") (pinfunction "2_2") (pintype "input"))
      (node (ref "U1") (pin "9") (pinfunction "PA4_9") (pintype "unspecified"))
      (node (ref "U18") (pin "1") (pinfunction "CSn_1") (pintype "unspecified"))
    )
    (net (code "10") (name "DVDD") (class "Default")
      (node (ref "C10") (pin "2") (pinfunction "2_2") (pintype "unspecified"))
      (node (ref "U2") (pin "36") (pinfunction "DVDD_36") (pintype "input"))
    )
    (net (code "11") (name "ENABLE") (class "Default")
      (node (ref "U1") (pin "13") (pinfunction "PB0_13") (pintype "unspecified"))
      (node (ref "U2") (pin "38") (pinfunction "INLA_38") (pintype "input"))
      (node (ref "U2") (pin "40") (pinfunction "INLB_40") (pintype "input"))
      (node (ref "U2") (pin "42") (pinfunction "INLC_42") (pintype "input"))
    )
    (net (code "12") (name "ENC_A") (class "Default")
      (node (ref "R17") (pin "2") (pinfunction "2_2") (pintype "input"))
      (node (ref "U1") (pin "30") (pinfunction "PB7_30") (pintype "unspecified"))
    )
    (net (code "13") (name "ENC_B") (class "Default")
      (node (ref "R18") (pin "2") (pinfunction "2_2") (pintype "input"))
      (node (ref "U1") (pin "29") (pinfunction "PB6_29") (pintype "unspecified"))
    )
    (net (code "14") (name "FB") (class "Default")
      (node (ref "R13") (pin "2") (pinfunction "2_2") (pintype "input"))
      (node (ref "R14") (pin "1") (pinfunction "1_1") (pintype "input"))
      (node (ref "U2") (pin "1") (pinfunction "FB_1") (pintype "input"))
    )
    (net (code "15") (name "FDCAN_RX") (class "Default")
      (node (ref "U1") (pin "21") (pinfunction "PA11_21") (pintype "unspecified"))
      (node (ref "U3") (pin "4") (pinfunction "RXD_4") (pintype "unspecified"))
    )
    (net (code "16") (name "FDCAN_TX") (class "Default")
      (node (ref "U1") (pin "22") (pinfunction "PA12_22") (pintype "unspecified"))
      (node (ref "U3") (pin "1") (pinfunction "TXD_1") (pintype "unspecified"))
    )
    (net (code "17") (name "GHA") (class "Default")
      (node (ref "U2") (pin "8") (pinfunction "GHA_8") (pintype "input"))
      (node (ref "U4") (pin "4") (pinfunction "G_4") (pintype "input"))
    )
    (net (code "18") (name "GHB") (class "Default")
      (node (ref "U2") (pin "17") (pinfunction "GHB_17") (pintype "input"))
      (node (ref "U6") (pin "4") (pinfunction "G_4") (pintype "input"))
    )
    (net (code "19") (name "GHC") (class "Default")
      (node (ref "U2") (pin "18") (pinfunction "GHC_18") (pintype "input"))
      (node (ref "U8") (pin "4") (pinfunction "G_4") (pintype "input"))
    )
    (net (code "20") (name "GLA") (class "Default")
      (node (ref "U2") (pin "10") (pinfunction "GLA_10") (pintype "input"))
      (node (ref "U5") (pin "4") (pinfunction "G_4") (pintype "input"))
    )
    (net (code "21") (name "GLB") (class "Default")
      (node (ref "U2") (pin "15") (pinfunction "GLB_15") (pintype "input"))
      (node (ref "U7") (pin "4") (pinfunction "G_4") (pintype "input"))
    )
    (net (code "22") (name "GLC") (class "Default")
      (node (ref "U2") (pin "20") (pinfunction "GLC_20") (pintype "input"))
      (node (ref "U9") (pin "4") (pinfunction "G_4") (pintype "input"))
    )
    (net (code "23") (name "GND") (class "Default")
      (node (ref "C1") (pin "1") (pinfunction "1_1") (pintype "input"))
      (node (ref "C10") (pin "1") (pinfunction "1_1") (pintype "unspecified"))
      (node (ref "C12") (pin "2") (pinfunction "2_2") (pintype "unspecified"))
      (node (ref "C13") (pin "2") (pinfunction "2_2") (pintype "unspecified"))
      (node (ref "C14") (pin "2") (pinfunction "2_2") (pintype "unspecified"))
      (node (ref "C2") (pin "1") (pinfunction "1_1") (pintype "input"))
      (node (ref "C55") (pin "1") (pinfunction "1_1") (pintype "unspecified"))
      (node (ref "C56") (pin "1") (pinfunction "1_1") (pintype "input"))
      (node (ref "C57") (pin "2") (pinfunction "2_2") (pintype "input"))
      (node (ref "C58") (pin "1") (pinfunction "1_1") (pintype "input"))
      (node (ref "C59") (pin "1") (pinfunction "1_1") (pintype "unspecified"))
      (node (ref "C9") (pin "1") (pinfunction "1_1") (pintype "input"))
      (node (ref "D1") (pin "2") (pinfunction "A_2") (pintype "input"))
      (node (ref "H1") (pin "6") (pinfunction "6_6") (pintype "input"))
      (node (ref "LED1") (pin "1") (pinfunction "-_1") (pintype "input"))
      (node (ref "R10") (pin "2") (pinfunction "2_2") (pintype "input"))
      (node (ref "R11") (pin "2") (pinfunction "2_2") (pintype "input"))
      (node (ref "R12") (pin "2") (pinfunction "2_2") (pintype "input"))
      (node (ref "R14") (pin "2") (pinfunction "2_2") (pintype "input"))
      (node (ref "R15") (pin "1") (pinfunction "1_1") (pintype "input"))
      (node (ref "R9") (pin "2") (pinfunction "2_2") (pintype "input"))
      (node (ref "U1") (pin "14") (pinfunction "VSSA_14") (pintype "unspecified"))
      (node (ref "U1") (pin "16") (pinfunction "VSS_16") (pintype "unspecified"))
      (node (ref "U1") (pin "31") (pinfunction "PB8-BOOT0_31") (pintype "unspecified"))
      (node (ref "U1") (pin "32") (pinfunction "VSS_32") (pintype "unspecified"))
      (node (ref "U10") (pin "2") (pinfunction "2_2") (pintype "unspecified"))
      (node (ref "U11") (pin "2") (pinfunction "2_2") (pintype "unspecified"))
      (node (ref "U12") (pin "2") (pinfunction "2_2") (pintype "unspecified"))
      (node (ref "U16") (pin "2") (pinfunction "2_2") (pintype "input"))
      (node (ref "U18") (pin "13") (pinfunction "GND_13") (pintype "unspecified"))
      (node (ref "U2") (pin "27") (pinfunction "DGND_27") (pintype "input"))
      (node (ref "U2") (pin "35") (pinfunction "AGND_35") (pintype "input"))
      (node (ref "U2") (pin "43") (pinfunction "BGND_43") (pintype "input"))
      (node (ref "U3") (pin "2") (pinfunction "GND_2") (pintype "unspecified"))
    )
    (net (code "24") (name "LP_SOA") (class "Default")
      (node (ref "C57") (pin "1") (pinfunction "1_1") (pintype "input"))
      (node (ref "U1") (pin "5") (pinfunction "PA0_5") (pintype "unspecified"))
      (node (ref "U14") (pin "2") (pinfunction "2_2") (pintype "unspecified"))
    )
    (net (code "25") (name "LP_SOB") (class "Default")
      (node (ref "C58") (pin "2") (pinfunction "2_2") (pintype "input"))
      (node (ref "U1") (pin "6") (pinfunction "PA1_6") (pintype "unspecified"))
      (node (ref "U15") (pin "2") (pinfunction "2_2") (pintype "unspecified"))
    )
    (net (code "26") (name "MISO_MAG") (class "Default")
      (node (ref "H1") (pin "3") (pinfunction "3_3") (pintype "input"))
      (node (ref "U1") (pin "11") (pinfunction "PA6_11") (pintype "unspecified"))
      (node (ref "U18") (pin "3") (pinfunction "MISO_3") (pintype "unspecified"))
    )
    (net (code "27") (name "MOSI_MAG") (class "Default")
      (node (ref "H1") (pin "4") (pinfunction "4_4") (pintype "input"))
      (node (ref "U1") (pin "12") (pinfunction "PA7_12") (pintype "unspecified"))
      (node (ref "U18") (pin "4") (pinfunction "MOSI_4") (pintype "unspecified"))
    )
    (net (code "28") (name "NFAULT") (class "Default")
      (node (ref "R7") (pin "1") (pinfunction "1_1") (pintype "input"))
      (node (ref "R8") (pin "1") (pinfunction "1_1") (pintype "input"))
      (node (ref "U2") (pin "28") (pinfunction "nFAULT_28") (pintype "input"))
    )
    (net (code "29") (name "Net-(D1-C)") (class "Default")
      (node (ref "C11") (pin "1") (pinfunction "1_1") (pintype "input"))
      (node (ref "D1") (pin "1") (pinfunction "C_1") (pintype "input"))
      (node (ref "L2") (pin "1") (pinfunction "1_1") (pintype "input"))
      (node (ref "U2") (pin "45") (pinfunction "SW_45") (pintype "input"))
    )
    (net (code "30") (name "Net-(LED1-+)") (class "Default")
      (node (ref "LED1") (pin "2") (pinfunction "+_2") (pintype "input"))
      (node (ref "R4") (pin "1") (pinfunction "1_1") (pintype "input"))
    )
    (net (code "31") (name "Net-(LED2--)") (class "Default")
      (node (ref "LED2") (pin "1") (pinfunction "-_1") (pintype "input"))
      (node (ref "R8") (pin "2") (pinfunction "2_2") (pintype "input"))
    )
    (net (code "32") (name "Net-(U2-CB)") (class "Default")
      (node (ref "C11") (pin "2") (pinfunction "2_2") (pintype "input"))
      (node (ref "U2") (pin "44") (pinfunction "CB_44") (pintype "input"))
    )
    (net (code "33") (name "Net-(U2-CPH)") (class "Default")
      (node (ref "C5") (pin "1") (pinfunction "1_1") (pintype "input"))
      (node (ref "U2") (pin "4") (pinfunction "CPH_4") (pintype "input"))
    )
    (net (code "34") (name "Net-(U2-CPL)") (class "Default")
      (node (ref "C5") (pin "2") (pinfunction "2_2") (pintype "input"))
      (node (ref "U2") (pin "3") (pinfunction "CPL_3") (pintype "input"))
    )
    (net (code "35") (name "Net-(U2-GAIN)") (class "Default")
      (node (ref "R10") (pin "1") (pinfunction "1_1") (pintype "input"))
      (node (ref "U2") (pin "32") (pinfunction "GAIN_32") (pintype "input"))
    )
    (net (code "36") (name "Net-(U2-IDRIVE)") (class "Default")
      (node (ref "R12") (pin "1") (pinfunction "1_1") (pintype "input"))
      (node (ref "U2") (pin "30") (pinfunction "IDRIVE_30") (pintype "input"))
    )
    (net (code "37") (name "Net-(U2-MODE)") (class "Default")
      (node (ref "R9") (pin "1") (pinfunction "1_1") (pintype "input"))
      (node (ref "U2") (pin "29") (pinfunction "MODE_29") (pintype "input"))
    )
    (net (code "38") (name "Net-(U2-VCP)") (class "Default")
      (node (ref "C8") (pin "2") (pinfunction "2_2") (pintype "unspecified"))
      (node (ref "U2") (pin "5") (pinfunction "VCP_5") (pintype "input"))
    )
    (net (code "39") (name "Net-(U2-VDS)") (class "Default")
      (node (ref "R11") (pin "1") (pinfunction "1_1") (pintype "input"))
      (node (ref "U2") (pin "31") (pinfunction "VDS_31") (pintype "input"))
    )
    (net (code "40") (name "PHASEA") (class "Default")
      (node (ref "U2") (pin "9") (pinfunction "SHA_9") (pintype "input"))
      (node (ref "U4") (pin "1") (pinfunction "S_1") (pintype "input"))
      (node (ref "U4") (pin "2") (pinfunction "S_2") (pintype "input"))
      (node (ref "U4") (pin "3") (pinfunction "S_3") (pintype "input"))
      (node (ref "U5") (pin "5") (pinfunction "D_5") (pintype "input"))
      (node (ref "U5") (pin "6") (pinfunction "D_6") (pintype "input"))
      (node (ref "U5") (pin "7") (pinfunction "D_7") (pintype "input"))
      (node (ref "U5") (pin "8") (pinfunction "D_8") (pintype "input"))
    )
    (net (code "41") (name "PHASEB") (class "Default")
      (node (ref "U2") (pin "16") (pinfunction "SHB_16") (pintype "input"))
      (node (ref "U6") (pin "1") (pinfunction "S_1") (pintype "input"))
      (node (ref "U6") (pin "2") (pinfunction "S_2") (pintype "input"))
      (node (ref "U6") (pin "3") (pinfunction "S_3") (pintype "input"))
      (node (ref "U7") (pin "5") (pinfunction "D_5") (pintype "input"))
      (node (ref "U7") (pin "6") (pinfunction "D_6") (pintype "input"))
      (node (ref "U7") (pin "7") (pinfunction "D_7") (pintype "input"))
      (node (ref "U7") (pin "8") (pinfunction "D_8") (pintype "input"))
    )
    (net (code "42") (name "PHASEC") (class "Default")
      (node (ref "U2") (pin "19") (pinfunction "SHC_19") (pintype "input"))
      (node (ref "U8") (pin "1") (pinfunction "S_1") (pintype "input"))
      (node (ref "U8") (pin "2") (pinfunction "S_2") (pintype "input"))
      (node (ref "U8") (pin "3") (pinfunction "S_3") (pintype "input"))
      (node (ref "U9") (pin "5") (pinfunction "D_5") (pintype "input"))
      (node (ref "U9") (pin "6") (pinfunction "D_6") (pintype "input"))
      (node (ref "U9") (pin "7") (pinfunction "D_7") (pintype "input"))
      (node (ref "U9") (pin "8") (pinfunction "D_8") (pintype "input"))
    )
    (net (code "43") (name "PWMA") (class "Default")
      (node (ref "U1") (pin "20") (pinfunction "PA10_20") (pintype "unspecified"))
      (node (ref "U2") (pin "37") (pinfunction "INHA_37") (pintype "input"))
    )
    (net (code "44") (name "PWMB") (class "Default")
      (node (ref "U1") (pin "19") (pinfunction "PA9_19") (pintype "unspecified"))
      (node (ref "U2") (pin "39") (pinfunction "INHB_39") (pintype "input"))
    )
    (net (code "45") (name "PWMC") (class "Default")
      (node (ref "U1") (pin "18") (pinfunction "PA8_18") (pintype "unspecified"))
      (node (ref "U2") (pin "41") (pinfunction "INHC_41") (pintype "input"))
    )
    (net (code "46") (name "SOA") (class "Default")
      (node (ref "U14") (pin "1") (pinfunction "1_1") (pintype "unspecified"))
      (node (ref "U2") (pin "25") (pinfunction "SOA_25") (pintype "input"))
    )
    (net (code "47") (name "SOB") (class "Default")
      (node (ref "U15") (pin "1") (pinfunction "1_1") (pintype "unspecified"))
      (node (ref "U2") (pin "24") (pinfunction "SOB_24") (pintype "input"))
    )
    (net (code "48") (name "SOC") (class "Default")
      (node (ref "U2") (pin "23") (pinfunction "SOC_23") (pintype "input"))
    )
    (net (code "49") (name "SPA") (class "Default")
      (node (ref "R5") (pin "2") (pinfunction "2_2") (pintype "input"))
      (node (ref "U2") (pin "11") (pinfunction "SPA_11") (pintype "input"))
      (node (ref "U5") (pin "1") (pinfunction "S_1") (pintype "input"))
      (node (ref "U5") (pin "2") (pinfunction "S_2") (pintype "input"))
      (node (ref "U5") (pin "3") (pinfunction "S_3") (pintype "input"))
    )
    (net (code "50") (name "SPB") (class "Default")
      (node (ref "R6") (pin "1") (pinfunction "1_1") (pintype "input"))
      (node (ref "U2") (pin "14") (pinfunction "SPB_14") (pintype "input"))
      (node (ref "U7") (pin "1") (pinfunction "S_1") (pintype "input"))
      (node (ref "U7") (pin "2") (pinfunction "S_2") (pintype "input"))
      (node (ref "U7") (pin "3") (pinfunction "S_3") (pintype "input"))
    )
    (net (code "51") (name "SWCLK") (class "Default")
      (node (ref "U1") (pin "24") (pinfunction "PA14_24") (pintype "unspecified"))
      (node (ref "U16") (pin "4") (pinfunction "4_4") (pintype "input"))
    )
    (net (code "52") (name "SWIO") (class "Default")
      (node (ref "U1") (pin "23") (pinfunction "PA13_23") (pintype "unspecified"))
      (node (ref "U16") (pin "3") (pinfunction "3_3") (pintype "input"))
    )
    (net (code "53") (name "SWO") (class "Default")
      (node (ref "U1") (pin "26") (pinfunction "PB3_26") (pintype "unspecified"))
      (node (ref "U16") (pin "5") (pinfunction "5_5") (pintype "input"))
    )
    (net (code "54") (name "unconnected-(U1-PA2-Pad7)") (class "Default")
      (node (ref "U1") (pin "7") (pinfunction "PA2_7") (pintype "unspecified"))
    )
    (net (code "55") (name "unconnected-(U1-PA3-Pad8)") (class "Default")
      (node (ref "U1") (pin "8") (pinfunction "PA3_8") (pintype "unspecified"))
    )
    (net (code "56") (name "unconnected-(U1-PA15-Pad25)") (class "Default")
      (node (ref "U1") (pin "25") (pinfunction "PA15_25") (pintype "unspecified"))
    )
    (net (code "57") (name "unconnected-(U1-PB4-Pad27)") (class "Default")
      (node (ref "U1") (pin "27") (pinfunction "PB4_27") (pintype "unspecified"))
    )
    (net (code "58") (name "unconnected-(U1-PB5-Pad28)") (class "Default")
      (node (ref "U1") (pin "28") (pinfunction "PB5_28") (pintype "unspecified"))
    )
    (net (code "59") (name "unconnected-(U1-PF0-OSC_IN-Pad2)") (class "Default")
      (node (ref "U1") (pin "2") (pinfunction "PF0-OSC_IN_2") (pintype "unspecified"))
    )
    (net (code "60") (name "unconnected-(U1-PF1-OSC_OUT-Pad3)") (class "Default")
      (node (ref "U1") (pin "3") (pinfunction "PF1-OSC_OUT_3") (pintype "unspecified"))
    )
    (net (code "61") (name "unconnected-(U1-PG10-NRST-Pad4)") (class "Default")
      (node (ref "U1") (pin "4") (pinfunction "PG10-NRST_4") (pintype "unspecified"))
    )
    (net (code "62") (name "unconnected-(U2-EP-Pad49)") (class "Default")
      (node (ref "U2") (pin "49") (pinfunction "EP_49") (pintype "input"))
    )
    (net (code "63") (name "unconnected-(U2-NC-Pad46)") (class "Default")
      (node (ref "U2") (pin "46") (pinfunction "NC_46") (pintype "input"))
    )
    (net (code "64") (name "unconnected-(U2-nSHDN-Pad48)") (class "Default")
      (node (ref "U2") (pin "48") (pinfunction "nSHDN_48") (pintype "input"))
    )
    (net (code "65") (name "unconnected-(U3-NC-Pad5)") (class "Default")
      (node (ref "U3") (pin "5") (pinfunction "NC_5") (pintype "unspecified"))
    )
    (net (code "66") (name "unconnected-(U3-NC-Pad8)") (class "Default")
      (node (ref "U3") (pin "8") (pinfunction "NC_8") (pintype "unspecified"))
    )
    (net (code "67") (name "unconnected-(U18-PWM-Pad14)") (class "Default")
      (node (ref "U18") (pin "14") (pinfunction "PWM_14") (pintype "unspecified"))
    )
    (net (code "68") (name "unconnected-(U18-TEST-Pad5)") (class "Default")
      (node (ref "U18") (pin "5") (pinfunction "TEST_5") (pintype "unspecified"))
    )
    (net (code "69") (name "unconnected-(U18-TEST-Pad6)") (class "Default")
      (node (ref "U18") (pin "6") (pinfunction "TEST_6") (pintype "unspecified"))
    )
    (net (code "70") (name "unconnected-(U18-TEST-Pad7)") (class "Default")
      (node (ref "U18") (pin "7") (pinfunction "TEST_7") (pintype "unspecified"))
    )
    (net (code "71") (name "unconnected-(U18-TEST-Pad8)") (class "Default")
      (node (ref "U18") (pin "8") (pinfunction "TEST_8") (pintype "unspecified"))
    )
    (net (code "72") (name "unconnected-(U18-TEST-Pad9)") (class "Default")
      (node (ref "U18") (pin "9") (pinfunction "TEST_9") (pintype "unspecified"))
    )
    (net (code "73") (name "unconnected-(U18-TEST-Pad10)") (class "Default")
      (node (ref "U18") (pin "10") (pinfunction "TEST_10") (pintype "unspecified"))
    )
    (net (code "74") (name "unconnected-(U18-VDD5V-Pad11)") (class "Default")
      (node (ref "U18") (pin "11") (pinfunction "VDD5V_11") (pintype "unspecified"))
    )
    (net (code "75") (name "unconnected-(U19-Pad3)") (class "Default")
      (node (ref "U19") (pin "3") (pinfunction "3_3") (pintype "unspecified"))
    )
    (net (code "76") (name "unconnected-(U19-Pad4)") (class "Default")
      (node (ref "U19") (pin "4") (pinfunction "4_4") (pintype "unspecified"))
    )
  )
)
